# Sheet3.net
KiCad netlist of a schematic drawn in Altium Designer
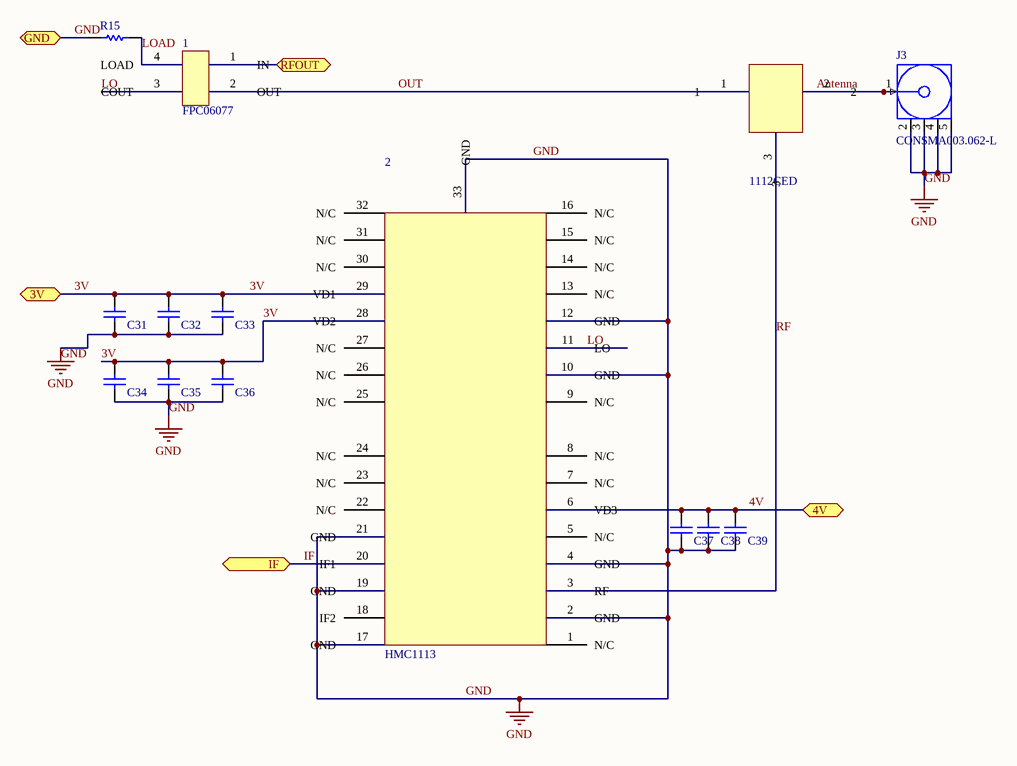
[diagram p0: Sheet3.SchDoc]

(export (version "E")
  (design (tool "Eeschema 10.0.6"))
  (components
    (comp (ref "1") (value "FPC06077") (footprint "FPC06077") (libsource (lib "FPC06077") (part "FPC06077")))
    (comp (ref "2")
      (value "HMC1113")
      (footprint "QFN50P500X500X5_HS-33N")
      (libsource (lib "HMC1113") (part "HMC1113"))
    )
    (comp (ref "1112CED")
      (value "~")
      (footprint "PCBComponent_1")
      (libsource (lib "1112CED") (part "Component_1"))
    )
    (comp (ref "C31")
      (value "CAP 2.2uF 16V 0603(1608)")
      (footprint "CAPC0603(1608)100_L")
      (description "CAP 2.2uF 16V ±1% 0603 (1608 Metric) Thickness 1mm SMD")
      (fields (field (name "TOLERANCE") "Â±1%"))
      (libsource (lib "Altium Content Vault") (part "CMP-1035-01744-1"))
    )
    (comp (ref "C32")
      (value "CAP 10nF 16V 0603(1608)")
      (footprint "CAPC0603(1608)100_L")
      (description "CAP 10nF 16V ±1% 0603 (1608 Metric) Thickness 1mm SMD")
      (fields (field (name "TOLERANCE") "Â±1%"))
      (libsource (lib "Altium Content Vault") (part "CMP-1035-01744-1"))
    )
    (comp (ref "C33")
      (value "CAP 100pF 16V 0603(1608)")
      (footprint "CAPC0603(1608)100_L")
      (description "CAP 100pF 16V ±1% 0603 (1608 Metric) Thickness 1mm SMD")
      (fields (field (name "TOLERANCE") "Â±1%"))
      (libsource (lib "Altium Content Vault") (part "CMP-1035-01744-1"))
    )
    (comp (ref "C34")
      (value "CAP 2.2uF 16V 0603(1608)")
      (footprint "CAPC0603(1608)100_L")
      (description "CAP 2.2uF 16V ±1% 0603 (1608 Metric) Thickness 1mm SMD")
      (fields (field (name "TOLERANCE") "Â±1%"))
      (libsource (lib "Altium Content Vault") (part "CMP-1035-01744-1"))
    )
    (comp (ref "C35")
      (value "CAP 10nF 16V 0603(1608)")
      (footprint "CAPC0603(1608)100_L")
      (description "CAP 10nF 16V ±1% 0603 (1608 Metric) Thickness 1mm SMD")
      (fields (field (name "TOLERANCE") "Â±1%"))
      (libsource (lib "Altium Content Vault") (part "CMP-1035-01744-1"))
    )
    (comp (ref "C36")
      (value "CAP 100pF 16V 0603(1608)")
      (footprint "CAPC0603(1608)100_L")
      (description "CAP 100pF 16V ±1% 0603 (1608 Metric) Thickness 1mm SMD")
      (fields (field (name "TOLERANCE") "Â±1%"))
      (libsource (lib "Altium Content Vault") (part "CMP-1035-01744-1"))
    )
    (comp (ref "C37")
      (value "CAP 100pF 16V 0603(1608)")
      (footprint "CAPC0603(1608)100_L")
      (description "CAP 100pF 16V ±1% 0603 (1608 Metric) Thickness 1mm SMD")
      (fields (field (name "TOLERANCE") "Â±1%"))
      (libsource (lib "Altium Content Vault") (part "CMP-1035-01744-1"))
    )
    (comp (ref "C38")
      (value "CAP 10nF 16V 0603(1608)")
      (footprint "CAPC0603(1608)100_L")
      (description "CAP 10nF 16V ±1% 0603 (1608 Metric) Thickness 1mm SMD")
      (fields (field (name "TOLERANCE") "Â±1%"))
      (libsource (lib "Altium Content Vault") (part "CMP-1035-01744-1"))
    )
    (comp (ref "C39")
      (value "CAP 2.2uF 16V 0603(1608)")
      (footprint "CAPC0603(1608)100_L")
      (description "CAP 2.2uF 16V ±1% 0603 (1608 Metric) Thickness 1mm SMD")
      (fields (field (name "TOLERANCE") "Â±1%"))
      (libsource (lib "Altium Content Vault") (part "CMP-1035-01744-1"))
    )
    (comp (ref "J3")
      (value "CONSMA003.062-L")
      (footprint "CON-SMA-EDGE062L")
      (libsource (lib "Altium Content Vault") (part "CMP-0168-00039-1"))
    )
    (comp (ref "R15")
      (value "50R 5% 0805(2012)")
      (footprint "RESC0805(2012)_N")
      (description "50R 0.125W 5% 0805 (2012 Metric)  SMD")
      (fields (field (name "POWER") "0.125 W") (field (name "TOLERANCE") "5 %"))
      (libsource (lib "Altium Content Vault") (part "CMP-1013-00037-1"))
    )
  )
  (nets
    (net (code "1") (name "/3V") (class "Default")
      (node (ref "2") (pin "28") (pinfunction "VD2_28") (pintype "passive"))
      (node (ref "2") (pin "29") (pinfunction "VD1_29") (pintype "passive"))
      (node (ref "C31") (pin "1") (pinfunction "1_1") (pintype "passive"))
      (node (ref "C32") (pin "1") (pinfunction "1_1") (pintype "passive"))
      (node (ref "C33") (pin "1") (pinfunction "1_1") (pintype "passive"))
      (node (ref "C34") (pin "1") (pinfunction "1_1") (pintype "passive"))
      (node (ref "C35") (pin "1") (pinfunction "1_1") (pintype "passive"))
      (node (ref "C36") (pin "1") (pinfunction "1_1") (pintype "passive"))
    )
    (net (code "2") (name "/4V") (class "Default")
      (node (ref "2") (pin "6") (pinfunction "VD3_6") (pintype "passive"))
      (node (ref "C37") (pin "1") (pinfunction "1_1") (pintype "passive"))
      (node (ref "C38") (pin "1") (pinfunction "1_1") (pintype "passive"))
      (node (ref "C39") (pin "1") (pinfunction "1_1") (pintype "passive"))
    )
    (net (code "3") (name "/Antenna") (class "Default")
      (node (ref "1112CED") (pin "2") (pinfunction "2_2") (pintype "passive"))
      (node (ref "J3") (pin "1") (pinfunction "Signal_1") (pintype "input"))
    )
    (net (code "4") (name "/IF") (class "Default")
      (node (ref "2") (pin "20") (pinfunction "IF1_20") (pintype "passive"))
    )
    (net (code "5") (name "/LO") (class "Default")
      (node (ref "1") (pin "3") (pinfunction "COUT_3") (pintype "passive"))
      (node (ref "2") (pin "11") (pinfunction "LO_11") (pintype "passive"))
    )
    (net (code "6") (name "/LOAD") (class "Default")
      (node (ref "1") (pin "4") (pinfunction "LOAD_4") (pintype "passive"))
      (node (ref "R15") (pin "2") (pinfunction "2_2") (pintype "passive"))
    )
    (net (code "7") (name "/OUT") (class "Default")
      (node (ref "1") (pin "2") (pinfunction "OUT_2") (pintype "passive"))
      (node (ref "1112CED") (pin "1") (pinfunction "1_1") (pintype "passive"))
    )
    (net (code "8") (name "/RF") (class "Default")
      (node (ref "1112CED") (pin "3") (pinfunction "3_3") (pintype "passive"))
      (node (ref "2") (pin "3") (pinfunction "RF_3") (pintype "passive"))
    )
    (net (code "9") (name "/RFOUT") (class "Default")
      (node (ref "1") (pin "1") (pinfunction "IN_1") (pintype "passive"))
    )
    (net (code "10") (name "GND") (class "Default")
      (node (ref "2") (pin "10") (pinfunction "GND_10") (pintype "passive"))
      (node (ref "2") (pin "12") (pinfunction "GND_12") (pintype "passive"))
      (node (ref "2") (pin "17") (pinfunction "GND_17") (pintype "passive"))
      (node (ref "2") (pin "19") (pinfunction "GND_19") (pintype "passive"))
      (node (ref "2") (pin "2") (pinfunction "GND_2") (pintype "passive"))
      (node (ref "2") (pin "21") (pinfunction "GND_21") (pintype "passive"))
      (node (ref "2") (pin "33") (pinfunction "GND_33") (pintype "passive"))
      (node (ref "2") (pin "4") (pinfunction "GND_4") (pintype "passive"))
      (node (ref "C31") (pin "2") (pinfunction "2_2") (pintype "passive"))
      (node (ref "C32") (pin "2") (pinfunction "2_2") (pintype "passive"))
      (node (ref "C33") (pin "2") (pinfunction "2_2") (pintype "passive"))
      (node (ref "C34") (pin "2") (pinfunction "2_2") (pintype "passive"))
      (node (ref "C35") (pin "2") (pinfunction "2_2") (pintype "passive"))
      (node (ref "C36") (pin "2") (pinfunction "2_2") (pintype "passive"))
      (node (ref "C37") (pin "2") (pinfunction "2_2") (pintype "passive"))
      (node (ref "C38") (pin "2") (pinfunction "2_2") (pintype "passive"))
      (node (ref "C39") (pin "2") (pinfunction "2_2") (pintype "passive"))
      (node (ref "J3") (pin "2") (pinfunction "GND_2") (pintype "power_in"))
      (node (ref "J3") (pin "3") (pinfunction "GND_3") (pintype "power_in"))
      (node (ref "J3") (pin "4") (pinfunction "GND_4") (pintype "power_in"))
      (node (ref "J3") (pin "5") (pinfunction "GND_5") (pintype "power_in"))
      (node (ref "R15") (pin "1") (pinfunction "1_1") (pintype "passive"))
    )
    (net (code "11") (name "unconnected-(2-IF2-Pad18)") (class "Default")
      (node (ref "2") (pin "18") (pinfunction "IF2_18") (pintype "passive"))
    )
    (net (code "12") (name "unconnected-(2-N{slash}C-Pad1)") (class "Default")
      (node (ref "2") (pin "1") (pinfunction "N/C_1") (pintype "passive"))
    )
    (net (code "13") (name "unconnected-(2-N{slash}C-Pad5)") (class "Default")
      (node (ref "2") (pin "5") (pinfunction "N/C_5") (pintype "passive"))
    )
    (net (code "14") (name "unconnected-(2-N{slash}C-Pad7)") (class "Default")
      (node (ref "2") (pin "7") (pinfunction "N/C_7") (pintype "passive"))
    )
    (net (code "15") (name "unconnected-(2-N{slash}C-Pad8)") (class "Default")
      (node (ref "2") (pin "8") (pinfunction "N/C_8") (pintype "passive"))
    )
    (net (code "16") (name "unconnected-(2-N{slash}C-Pad9)") (class "Default")
      (node (ref "2") (pin "9") (pinfunction "N/C_9") (pintype "passive"))
    )
    (net (code "17") (name "unconnected-(2-N{slash}C-Pad13)") (class "Default")
      (node (ref "2") (pin "13") (pinfunction "N/C_13") (pintype "passive"))
    )
    (net (code "18") (name "unconnected-(2-N{slash}C-Pad14)") (class "Default")
      (node (ref "2") (pin "14") (pinfunction "N/C_14") (pintype "passive"))
    )
    (net (code "19") (name "unconnected-(2-N{slash}C-Pad15)") (class "Default")
      (node (ref "2") (pin "15") (pinfunction "N/C_15") (pintype "passive"))
    )
    (net (code "20") (name "unconnected-(2-N{slash}C-Pad16)") (class "Default")
      (node (ref "2") (pin "16") (pinfunction "N/C_16") (pintype "passive"))
    )
    (net (code "21") (name "unconnected-(2-N{slash}C-Pad22)") (class "Default")
      (node (ref "2") (pin "22") (pinfunction "N/C_22") (pintype "passive"))
    )
    (net (code "22") (name "unconnected-(2-N{slash}C-Pad23)") (class "Default")
      (node (ref "2") (pin "23") (pinfunction "N/C_23") (pintype "passive"))
    )
    (net (code "23") (name "unconnected-(2-N{slash}C-Pad24)") (class "Default")
      (node (ref "2") (pin "24") (pinfunction "N/C_24") (pintype "passive"))
    )
    (net (code "24") (name "unconnected-(2-N{slash}C-Pad25)") (class "Default")
      (node (ref "2") (pin "25") (pinfunction "N/C_25") (pintype "passive"))
    )
    (net (code "25") (name "unconnected-(2-N{slash}C-Pad26)") (class "Default")
      (node (ref "2") (pin "26") (pinfunction "N/C_26") (pintype "passive"))
    )
    (net (code "26") (name "unconnected-(2-N{slash}C-Pad27)") (class "Default")
      (node (ref "2") (pin "27") (pinfunction "N/C_27") (pintype "passive"))
    )
    (net (code "27") (name "unconnected-(2-N{slash}C-Pad30)") (class "Default")
      (node (ref "2") (pin "30") (pinfunction "N/C_30") (pintype "passive"))
    )
    (net (code "28") (name "unconnected-(2-N{slash}C-Pad31)") (class "Default")
      (node (ref "2") (pin "31") (pinfunction "N/C_31") (pintype "passive"))
    )
    (net (code "29") (name "unconnected-(2-N{slash}C-Pad32)") (class "Default")
      (node (ref "2") (pin "32") (pinfunction "N/C_32") (pintype "passive"))
    )
  )
)
